# Optosense.net
KiCad netlist of a schematic drawn in Altium Designer
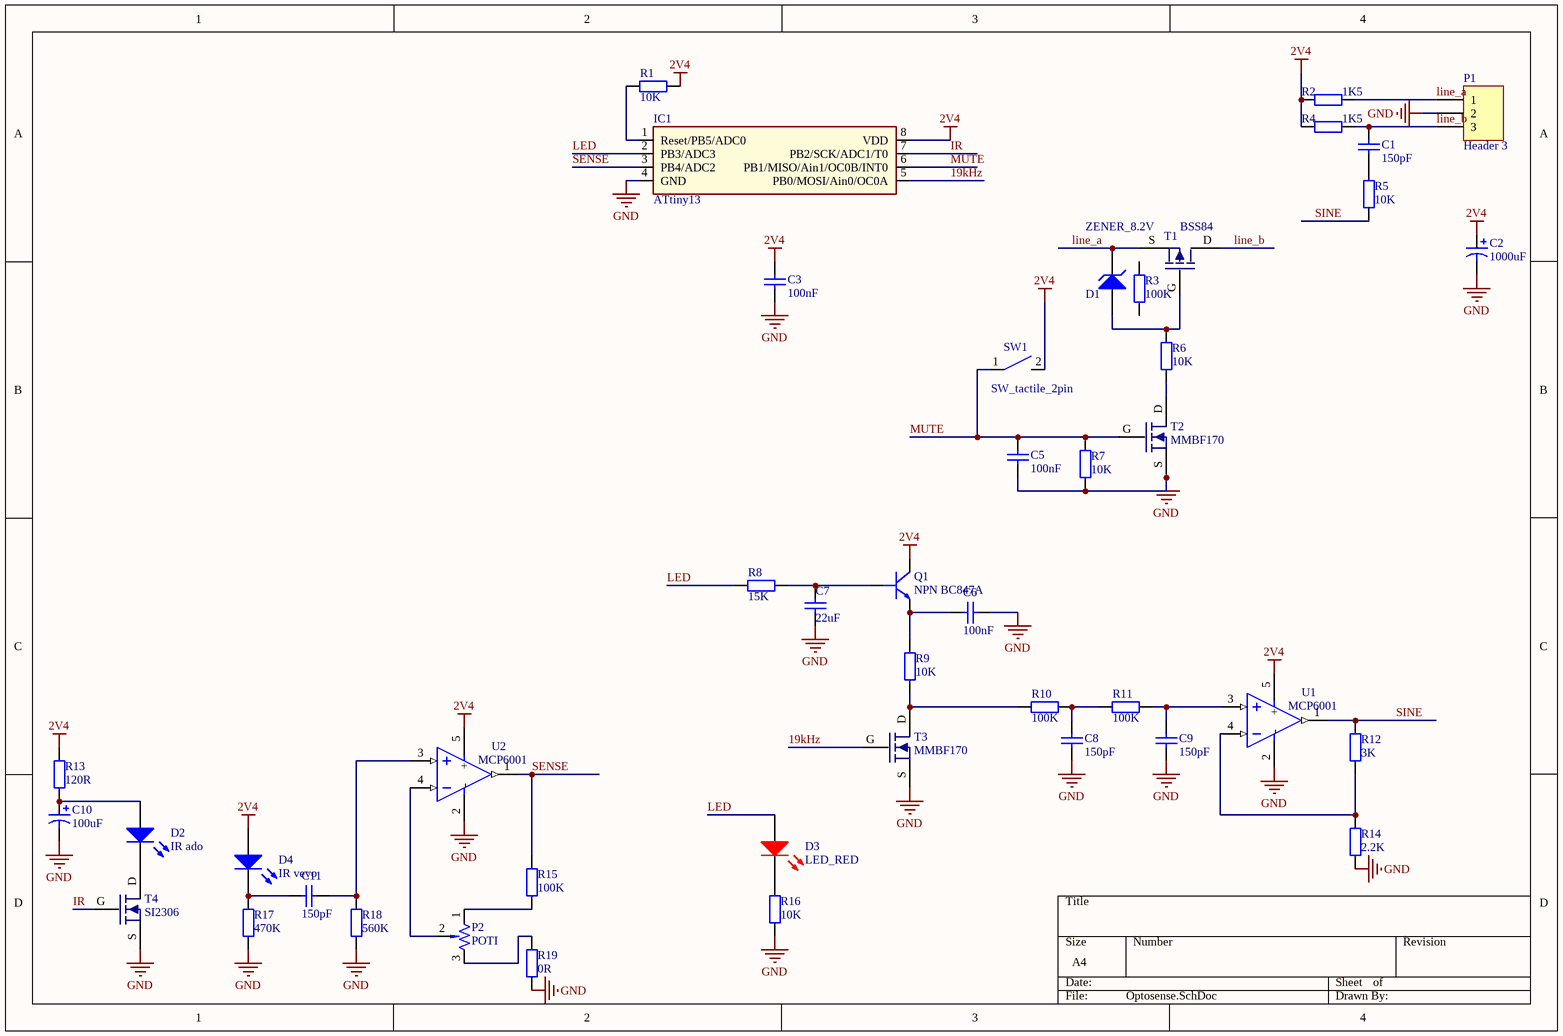
[diagram p0: Optosense.SchDoc]

(export (version "E")
  (design (tool "Eeschema 10.0.6"))
  (components
    (comp (ref "C1")
      (value "150pF")
      (footprint "FP_0603_CAP_080")
      (description "Capacitor")
      (libsource (lib "Capacitor") (part "CAP"))
    )
    (comp (ref "C2")
      (value "1000uF")
      (footprint "CAP_8x11_fekvo")
      (description "Polarized Capacitor")
      (libsource (lib "Capacitor") (part "CAP_ELECT"))
    )
    (comp (ref "C3")
      (value "100nF")
      (footprint "FP_0603_CAP_080")
      (description "Capacitor")
      (libsource (lib "Capacitor") (part "CAP"))
    )
    (comp (ref "C5")
      (value "100nF")
      (footprint "FP_0603_CAP_080")
      (description "Capacitor")
      (libsource (lib "Capacitor") (part "CAP"))
    )
    (comp (ref "C6")
      (value "100nF")
      (footprint "FP_0603_CAP_080")
      (description "Capacitor")
      (libsource (lib "Capacitor") (part "CAP"))
    )
    (comp (ref "C7")
      (value "22uF")
      (footprint "FP_1206_CAP_125")
      (description "Capacitor")
      (libsource (lib "Miscellaneous Devices") (part "Cap"))
    )
    (comp (ref "C8")
      (value "150pF")
      (footprint "FP_0603_CAP_080")
      (description "Capacitor")
      (libsource (lib "Capacitor") (part "CAP"))
    )
    (comp (ref "C9")
      (value "150pF")
      (footprint "FP_0603_CAP_080")
      (description "Capacitor")
      (libsource (lib "Capacitor") (part "CAP"))
    )
    (comp (ref "C10")
      (value "100uF")
      (footprint "FP_3528")
      (description "Polarized Capacitor")
      (libsource (lib "Capacitor") (part "CAP_ELECT"))
    )
    (comp (ref "C11")
      (value "150pF")
      (footprint "FP_0603_CAP_080")
      (description "Capacitor")
      (libsource (lib "Capacitor") (part "CAP"))
    )
    (comp (ref "D1")
      (value "ZENER_8.2V")
      (footprint "SOD-80")
      (description "Zener Diode")
      (libsource (lib "Diode") (part "ZENER"))
    )
    (comp (ref "D2")
      (value "IR ado")
      (footprint "LED_IR_5mm")
      (description "Typical LED")
      (libsource (lib "Led_optical") (part "LED_B"))
    )
    (comp (ref "D3")
      (value "LED_RED")
      (footprint "led_3mm_standing R")
      (description "Typical LED")
      (libsource (lib "Led_optical") (part "LED_R"))
    )
    (comp (ref "D4")
      (value "IR vevo")
      (footprint "LED_IR_5mm")
      (description "Typical LED")
      (libsource (lib "Led_optical") (part "LED_B"))
    )
    (comp (ref "IC1") (value "ATtiny13") (footprint "WSON_n_SOIC8") (libsource (lib "uC") (part "ATtiny13")))
    (comp (ref "P1")
      (value "Header 3")
      (footprint "HDR1X3")
      (description "Header, 3-Pin")
      (fields (field (name "PUBLISHER") "Altium Limited"))
      (libsource (lib "Miscellaneous Connectors") (part "Header 3"))
    )
    (comp (ref "P2")
      (value "POTI")
      (footprint "RES_trimmer_helipot_mini_90")
      (libsource (lib "Resistor") (part "POTI"))
    )
    (comp (ref "Q1") (value "NPN BC847A") (footprint "TR_SOT23") (libsource (lib "Transistor") (part "NPN")))
    (comp (ref "R1")
      (value "10K")
      (footprint "FP_0603_RES")
      (description "Resistor")
      (libsource (lib "Resistor") (part "RES"))
    )
    (comp (ref "R2")
      (value "1K5")
      (footprint "FP_0603_RES")
      (description "Resistor")
      (libsource (lib "") (part "RES_3"))
    )
    (comp (ref "R3")
      (value "100K")
      (footprint "FP_0603_RES")
      (description "Resistor")
      (libsource (lib "") (part "RES_1"))
    )
    (comp (ref "R4")
      (value "1K5")
      (footprint "FP_0603_RES")
      (description "Resistor")
      (libsource (lib "") (part "RES_3"))
    )
    (comp (ref "R5")
      (value "10K")
      (footprint "FP_0603_RES")
      (description "Resistor")
      (libsource (lib "") (part "RES_2"))
    )
    (comp (ref "R6")
      (value "10K")
      (footprint "FP_0603_RES")
      (description "Resistor")
      (libsource (lib "") (part "RES_1"))
    )
    (comp (ref "R7")
      (value "10K")
      (footprint "FP_0603_RES")
      (description "Resistor")
      (libsource (lib "") (part "RES_1"))
    )
    (comp (ref "R8")
      (value "15K")
      (footprint "FP_0603_RES")
      (description "Resistor")
      (libsource (lib "Resistor") (part "RES"))
    )
    (comp (ref "R9")
      (value "10K")
      (footprint "FP_0603_RES")
      (description "Resistor")
      (libsource (lib "") (part "RES_1"))
    )
    (comp (ref "R10")
      (value "100K")
      (footprint "FP_0603_RES")
      (description "Resistor")
      (libsource (lib "Resistor") (part "RES"))
    )
    (comp (ref "R11")
      (value "100K")
      (footprint "FP_0603_RES")
      (description "Resistor")
      (libsource (lib "Resistor") (part "RES"))
    )
    (comp (ref "R12")
      (value "3K")
      (footprint "FP_0603_RES")
      (description "Resistor")
      (libsource (lib "") (part "RES_1"))
    )
    (comp (ref "R13")
      (value "120R")
      (footprint "FP_0603_RES")
      (description "Resistor")
      (libsource (lib "") (part "RES_2"))
    )
    (comp (ref "R14")
      (value "2.2K")
      (footprint "FP_0603_RES")
      (description "Resistor")
      (libsource (lib "") (part "RES_1"))
    )
    (comp (ref "R15")
      (value "100K")
      (footprint "FP_0603_RES")
      (description "Resistor")
      (libsource (lib "") (part "RES_2"))
    )
    (comp (ref "R16")
      (value "10K")
      (footprint "FP_0603_RES")
      (description "Resistor")
      (libsource (lib "") (part "RES_2"))
    )
    (comp (ref "R17")
      (value "470K")
      (footprint "FP_0603_RES")
      (description "Resistor")
      (libsource (lib "") (part "RES_2"))
    )
    (comp (ref "R18")
      (value "560K")
      (footprint "FP_0603_RES")
      (description "Resistor")
      (libsource (lib "") (part "RES_2"))
    )
    (comp (ref "R19")
      (value "0R")
      (footprint "FP_0603_RES")
      (description "Resistor")
      (libsource (lib "") (part "RES_2"))
    )
    (comp (ref "SW1")
      (value "SW_tactile_2pin")
      (footprint "SW_TACT_2PIN")
      (libsource (lib "Switch") (part "SW_tactile_2pin"))
    )
    (comp (ref "T1") (value "BSS84") (footprint "FET_SOT23") (libsource (lib "FET") (part "PMOS")))
    (comp (ref "T2") (value "MMBF170") (footprint "FET_SOT23") (libsource (lib "FET") (part "NMOS")))
    (comp (ref "T3") (value "MMBF170") (footprint "FET_SOT23") (libsource (lib "FET") (part "NMOS")))
    (comp (ref "T4") (value "SI2306") (footprint "FET_SOT23") (libsource (lib "FET") (part "NMOS")))
    (comp (ref "U1")
      (value "MCP6001")
      (footprint "ANALOG_SOT23-5")
      (libsource (lib "Analog") (part "MCP6001"))
    )
    (comp (ref "U2")
      (value "MCP6001")
      (footprint "ANALOG_SOT23-5")
      (libsource (lib "Analog") (part "MCP6001"))
    )
  )
  (nets
    (net (code "1") (name "/19kHz") (class "Default")
      (node (ref "IC1") (pin "5") (pinfunction "PB0/MOSI/Ain0/OC0A_5") (pintype "passive"))
      (node (ref "T3") (pin "G") (pinfunction "G_G") (pintype "passive"))
    )
    (net (code "2") (name "/IR") (class "Default")
      (node (ref "IC1") (pin "7") (pinfunction "PB2/SCK/ADC1/T0_7") (pintype "passive"))
      (node (ref "T4") (pin "G") (pinfunction "G_G") (pintype "passive"))
    )
    (net (code "3") (name "/LED") (class "Default")
      (node (ref "D3") (pin "A") (pinfunction "A_A") (pintype "passive"))
      (node (ref "IC1") (pin "2") (pinfunction "PB3/ADC3_2") (pintype "passive"))
      (node (ref "R8") (pin "2") (pinfunction "2_2") (pintype "passive"))
    )
    (net (code "4") (name "/MUTE") (class "Default")
      (node (ref "C5") (pin "2") (pinfunction "2_2") (pintype "passive"))
      (node (ref "IC1") (pin "6") (pinfunction "PB1/MISO/Ain1/OC0B/INT0_6") (pintype "passive"))
      (node (ref "R7") (pin "1") (pinfunction "1_1") (pintype "passive"))
      (node (ref "SW1") (pin "1") (pinfunction "1_1") (pintype "passive"))
      (node (ref "T2") (pin "G") (pinfunction "G_G") (pintype "passive"))
    )
    (net (code "5") (name "/SENSE") (class "Default")
      (node (ref "IC1") (pin "3") (pinfunction "PB4/ADC2_3") (pintype "passive"))
      (node (ref "R15") (pin "2") (pinfunction "2_2") (pintype "passive"))
      (node (ref "U2") (pin "1") (pinfunction "OUT1_1") (pintype "output"))
    )
    (net (code "6") (name "/SINE") (class "Default")
      (node (ref "R12") (pin "1") (pinfunction "1_1") (pintype "passive"))
      (node (ref "R5") (pin "1") (pinfunction "1_1") (pintype "passive"))
      (node (ref "U1") (pin "1") (pinfunction "OUT1_1") (pintype "output"))
    )
    (net (code "7") (name "/line_a") (class "Default")
      (node (ref "D1") (pin "K") (pinfunction "K_K") (pintype "passive"))
      (node (ref "P1") (pin "1") (pinfunction "1_1") (pintype "passive"))
      (node (ref "R2") (pin "2") (pinfunction "2_2") (pintype "passive"))
      (node (ref "T1") (pin "S") (pinfunction "S_S") (pintype "passive"))
    )
    (net (code "8") (name "/line_b") (class "Default")
      (node (ref "C1") (pin "2") (pinfunction "2_2") (pintype "passive"))
      (node (ref "P1") (pin "3") (pinfunction "3_3") (pintype "passive"))
      (node (ref "R4") (pin "2") (pinfunction "2_2") (pintype "passive"))
      (node (ref "T1") (pin "D") (pinfunction "D_D") (pintype "passive"))
    )
    (net (code "9") (name "2V4") (class "Default")
      (node (ref "C2") (pin "P") (pintype "passive"))
      (node (ref "C3") (pin "2") (pinfunction "2_2") (pintype "passive"))
      (node (ref "D4") (pin "A") (pinfunction "A_A") (pintype "passive"))
      (node (ref "IC1") (pin "8") (pinfunction "VDD_8") (pintype "passive"))
      (node (ref "Q1") (pin "C") (pinfunction "C_C") (pintype "passive"))
      (node (ref "R1") (pin "1") (pinfunction "1_1") (pintype "passive"))
      (node (ref "R13") (pin "2") (pinfunction "2_2") (pintype "passive"))
      (node (ref "R2") (pin "1") (pinfunction "1_1") (pintype "passive"))
      (node (ref "R4") (pin "1") (pinfunction "1_1") (pintype "passive"))
      (node (ref "SW1") (pin "2") (pinfunction "2_2") (pintype "passive"))
      (node (ref "U1") (pin "5") (pinfunction "+_5") (pintype "power_in"))
      (node (ref "U2") (pin "5") (pinfunction "+_5") (pintype "power_in"))
    )
    (net (code "10") (name "GND") (class "Default")
      (node (ref "C10") (pin "N") (pintype "passive"))
      (node (ref "C2") (pin "N") (pintype "passive"))
      (node (ref "C3") (pin "1") (pinfunction "1_1") (pintype "passive"))
      (node (ref "C5") (pin "1") (pinfunction "1_1") (pintype "passive"))
      (node (ref "C6") (pin "1") (pinfunction "1_1") (pintype "passive"))
      (node (ref "C7") (pin "1") (pinfunction "1_1") (pintype "passive"))
      (node (ref "C8") (pin "1") (pinfunction "1_1") (pintype "passive"))
      (node (ref "C9") (pin "1") (pinfunction "1_1") (pintype "passive"))
      (node (ref "IC1") (pin "4") (pinfunction "GND_4") (pintype "passive"))
      (node (ref "P1") (pin "2") (pinfunction "2_2") (pintype "passive"))
      (node (ref "R14") (pin "2") (pinfunction "2_2") (pintype "passive"))
      (node (ref "R16") (pin "1") (pinfunction "1_1") (pintype "passive"))
      (node (ref "R17") (pin "1") (pinfunction "1_1") (pintype "passive"))
      (node (ref "R18") (pin "1") (pinfunction "1_1") (pintype "passive"))
      (node (ref "R19") (pin "1") (pinfunction "1_1") (pintype "passive"))
      (node (ref "R7") (pin "2") (pinfunction "2_2") (pintype "passive"))
      (node (ref "T2") (pin "S") (pinfunction "S_S") (pintype "passive"))
      (node (ref "T3") (pin "S") (pinfunction "S_S") (pintype "passive"))
      (node (ref "T4") (pin "S") (pinfunction "S_S") (pintype "passive"))
      (node (ref "U1") (pin "2") (pinfunction "-_2") (pintype "power_in"))
      (node (ref "U2") (pin "2") (pinfunction "-_2") (pintype "power_in"))
    )
    (net (code "11") (name "Net-(C1-Pad1)") (class "Default")
      (node (ref "C1") (pin "1") (pinfunction "1_1") (pintype "passive"))
      (node (ref "R5") (pin "2") (pinfunction "2_2") (pintype "passive"))
    )
    (net (code "12") (name "Net-(C6-Pad2)") (class "Default")
      (node (ref "C6") (pin "2") (pinfunction "2_2") (pintype "passive"))
      (node (ref "Q1") (pin "E") (pinfunction "E_E") (pintype "passive"))
      (node (ref "R9") (pin "1") (pinfunction "1_1") (pintype "passive"))
    )
    (net (code "13") (name "Net-(C7-Pad2)") (class "Default")
      (node (ref "C7") (pin "2") (pinfunction "2_2") (pintype "passive"))
      (node (ref "Q1") (pin "B") (pinfunction "B_B") (pintype "passive"))
      (node (ref "R8") (pin "1") (pinfunction "1_1") (pintype "passive"))
    )
    (net (code "14") (name "Net-(C8-Pad2)") (class "Default")
      (node (ref "C8") (pin "2") (pinfunction "2_2") (pintype "passive"))
      (node (ref "R10") (pin "1") (pinfunction "1_1") (pintype "passive"))
      (node (ref "R11") (pin "2") (pinfunction "2_2") (pintype "passive"))
    )
    (net (code "15") (name "Net-(C10-PadP)") (class "Default")
      (node (ref "C10") (pin "P") (pintype "passive"))
      (node (ref "D2") (pin "A") (pinfunction "A_A") (pintype "passive"))
      (node (ref "R13") (pin "1") (pinfunction "1_1") (pintype "passive"))
    )
    (net (code "16") (name "Net-(C11-Pad1)") (class "Default")
      (node (ref "C11") (pin "1") (pinfunction "1_1") (pintype "passive"))
      (node (ref "D4") (pin "K") (pinfunction "K_K") (pintype "passive"))
      (node (ref "R17") (pin "2") (pinfunction "2_2") (pintype "passive"))
    )
    (net (code "17") (name "Net-(D1-PadA)") (class "Default")
      (node (ref "D1") (pin "A") (pinfunction "A_A") (pintype "passive"))
      (node (ref "R6") (pin "1") (pinfunction "1_1") (pintype "passive"))
      (node (ref "T1") (pin "G") (pinfunction "G_G") (pintype "passive"))
    )
    (net (code "18") (name "Net-(D2-PadK)") (class "Default")
      (node (ref "D2") (pin "K") (pinfunction "K_K") (pintype "passive"))
      (node (ref "T4") (pin "D") (pinfunction "D_D") (pintype "passive"))
    )
    (net (code "19") (name "Net-(D3-PadK)") (class "Default")
      (node (ref "D3") (pin "K") (pinfunction "K_K") (pintype "passive"))
      (node (ref "R16") (pin "2") (pinfunction "2_2") (pintype "passive"))
    )
    (net (code "20") (name "Net-(IC1-Reset{slash}PB5{slash}ADC0)") (class "Default")
      (node (ref "IC1") (pin "1") (pinfunction "Reset/PB5/ADC0_1") (pintype "passive"))
      (node (ref "R1") (pin "2") (pinfunction "2_2") (pintype "passive"))
    )
    (net (code "21") (name "Net-(P2-2)") (class "Default")
      (node (ref "P2") (pin "3") (pinfunction "2_3") (pintype "passive"))
      (node (ref "R19") (pin "2") (pinfunction "2_2") (pintype "passive"))
    )
    (net (code "22") (name "Net-(P2-Pad1)") (class "Default")
      (node (ref "P2") (pin "1") (pinfunction "1_1") (pintype "passive"))
      (node (ref "R15") (pin "1") (pinfunction "1_1") (pintype "passive"))
    )
    (net (code "23") (name "Net-(P2-t)") (class "Default")
      (node (ref "P2") (pin "2") (pinfunction "t_2") (pintype "passive"))
      (node (ref "U2") (pin "4") (pinfunction "IN1-_4") (pintype "input"))
    )
    (net (code "24") (name "Net-(R6-Pad2)") (class "Default")
      (node (ref "R6") (pin "2") (pinfunction "2_2") (pintype "passive"))
      (node (ref "T2") (pin "D") (pinfunction "D_D") (pintype "passive"))
    )
    (net (code "25") (name "Net-(R10-Pad2)") (class "Default")
      (node (ref "R10") (pin "2") (pinfunction "2_2") (pintype "passive"))
      (node (ref "R9") (pin "2") (pinfunction "2_2") (pintype "passive"))
      (node (ref "T3") (pin "D") (pinfunction "D_D") (pintype "passive"))
    )
    (net (code "26") (name "Net-(U1-IN1+)") (class "Default")
      (node (ref "C9") (pin "2") (pinfunction "2_2") (pintype "passive"))
      (node (ref "R11") (pin "1") (pinfunction "1_1") (pintype "passive"))
      (node (ref "U1") (pin "3") (pinfunction "IN1+_3") (pintype "input"))
    )
    (net (code "27") (name "Net-(U1-IN1-)") (class "Default")
      (node (ref "R12") (pin "2") (pinfunction "2_2") (pintype "passive"))
      (node (ref "R14") (pin "1") (pinfunction "1_1") (pintype "passive"))
      (node (ref "U1") (pin "4") (pinfunction "IN1-_4") (pintype "input"))
    )
    (net (code "28") (name "Net-(U2-IN1+)") (class "Default")
      (node (ref "C11") (pin "2") (pinfunction "2_2") (pintype "passive"))
      (node (ref "R18") (pin "2") (pinfunction "2_2") (pintype "passive"))
      (node (ref "U2") (pin "3") (pinfunction "IN1+_3") (pintype "input"))
    )
    (net (code "29") (name "unconnected-(R3-Pad1)") (class "Default")
      (node (ref "R3") (pin "1") (pinfunction "1_1") (pintype "passive"))
    )
    (net (code "30") (name "unconnected-(R3-Pad2)") (class "Default")
      (node (ref "R3") (pin "2") (pinfunction "2_2") (pintype "passive"))
    )
  )
)
